# 8chADC.net
KiCad netlist of a schematic drawn in EAGLE
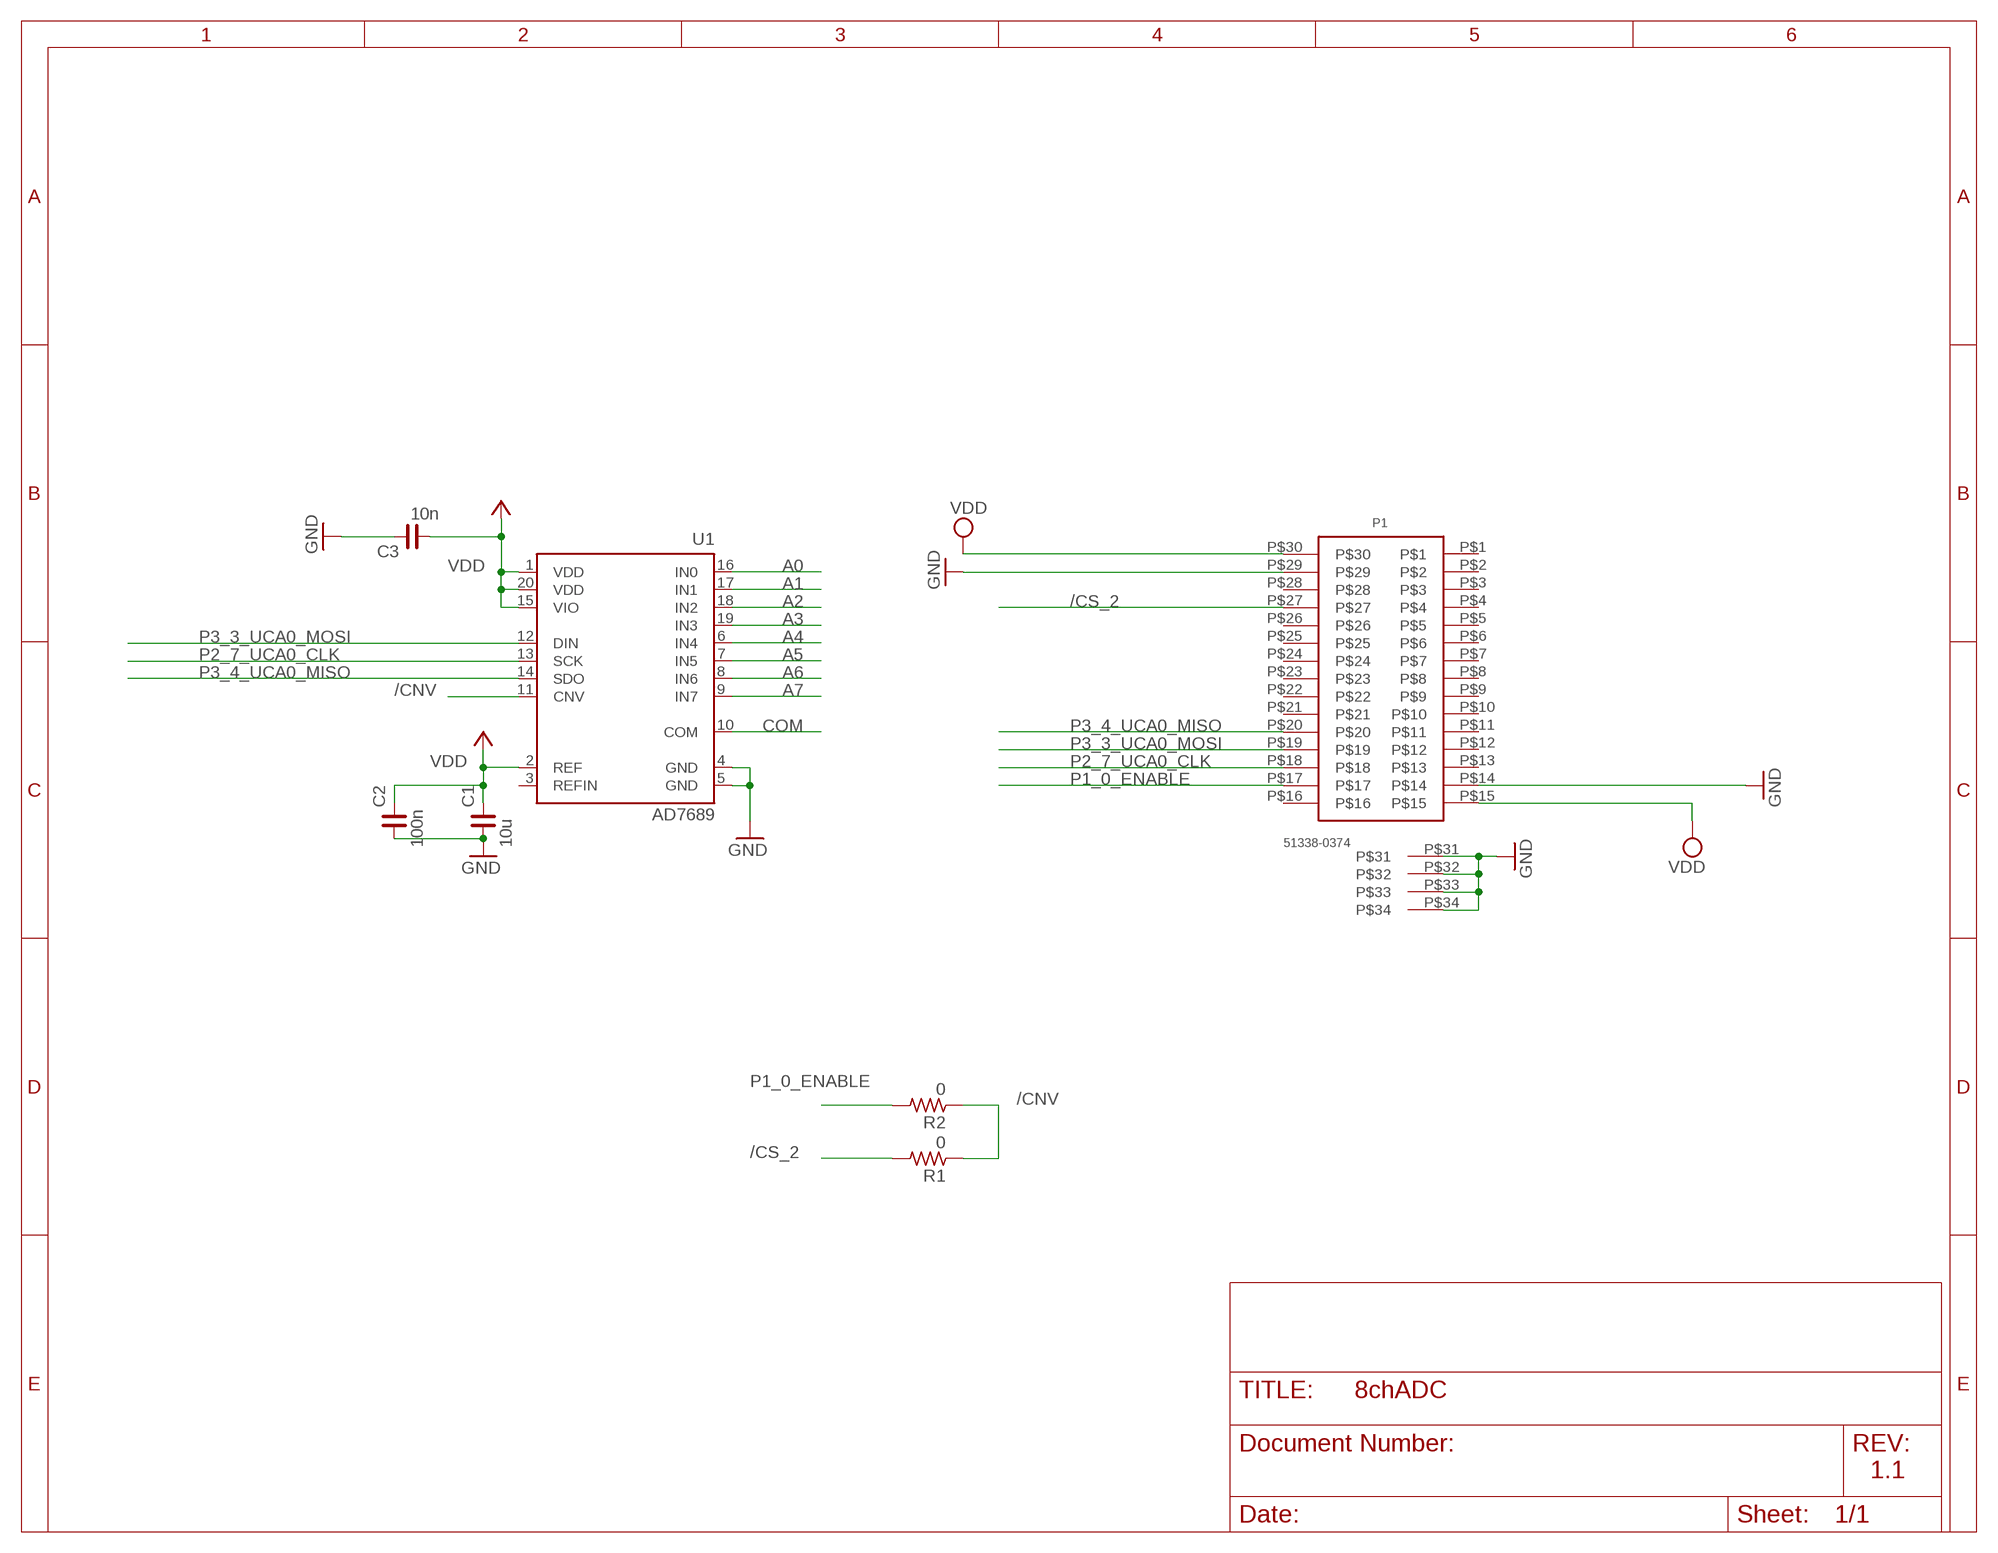
[diagram p0: schematic, sheet 1]

(export (version "E")
  (design (tool "Eeschema 10.0.6"))
  (components
    (comp (ref "C1")
      (value "10u")
      (footprint "eagle-import:C0402")
      (libsource (lib "eagle-import") (part "C_0402"))
    )
    (comp (ref "C2")
      (value "100n")
      (footprint "eagle-import:C0402")
      (libsource (lib "eagle-import") (part "C_0402"))
    )
    (comp (ref "C3")
      (value "10n")
      (footprint "eagle-import:C0402")
      (libsource (lib "eagle-import") (part "C_0402"))
    )
    (comp (ref "P1")
      (value "51338-0374")
      (footprint "eagle-import:51338-0374_RECEPTACLE")
      (libsource (lib "eagle-import") (part "51338-0374_RECEPTACLE"))
    )
    (comp (ref "R1")
      (value "0")
      (footprint "eagle-import:R0402")
      (libsource (lib "eagle-import") (part "R_0402"))
    )
    (comp (ref "R2")
      (value "0")
      (footprint "eagle-import:R0402")
      (libsource (lib "eagle-import") (part "R_0402"))
    )
    (comp (ref "U1")
      (value "AD7689")
      (footprint "eagle-import:LFCSP20")
      (libsource (lib "eagle-import") (part "AD7689"))
    )
  )
  (nets
    (net (code "1") (name "+3V3") (class "Default")
      (node (ref "C1") (pin "2") (pinfunction "2_2") (pintype "passive"))
      (node (ref "C2") (pin "2") (pinfunction "2_2") (pintype "passive"))
      (node (ref "C3") (pin "1") (pinfunction "1_1") (pintype "passive"))
      (node (ref "P1") (pin "P$15") (pinfunction "P$15_P$15") (pintype "bidirectional"))
      (node (ref "P1") (pin "P$30") (pinfunction "P$30_P$30") (pintype "bidirectional"))
      (node (ref "U1") (pin "1") (pinfunction "VDD_1") (pintype "power_in"))
      (node (ref "U1") (pin "15") (pinfunction "VIO_15") (pintype "power_in"))
      (node (ref "U1") (pin "2") (pinfunction "REF_2") (pintype "bidirectional"))
      (node (ref "U1") (pin "20") (pinfunction "VDD_20") (pintype "power_in"))
    )
    (net (code "2") (name "/A0") (class "Default")
      (node (ref "U1") (pin "16") (pinfunction "IN0_16") (pintype "input"))
    )
    (net (code "3") (name "/A1") (class "Default")
      (node (ref "U1") (pin "17") (pinfunction "IN1_17") (pintype "input"))
    )
    (net (code "4") (name "/A2") (class "Default")
      (node (ref "U1") (pin "18") (pinfunction "IN2_18") (pintype "input"))
    )
    (net (code "5") (name "/A3") (class "Default")
      (node (ref "U1") (pin "19") (pinfunction "IN3_19") (pintype "input"))
    )
    (net (code "6") (name "/A4") (class "Default")
      (node (ref "U1") (pin "6") (pinfunction "IN4_6") (pintype "input"))
    )
    (net (code "7") (name "/A5") (class "Default")
      (node (ref "U1") (pin "7") (pinfunction "IN5_7") (pintype "input"))
    )
    (net (code "8") (name "/A6") (class "Default")
      (node (ref "U1") (pin "8") (pinfunction "IN6_8") (pintype "input"))
    )
    (net (code "9") (name "/A7") (class "Default")
      (node (ref "U1") (pin "9") (pinfunction "IN7_9") (pintype "input"))
    )
    (net (code "10") (name "/COM") (class "Default")
      (node (ref "U1") (pin "10") (pinfunction "COM_10") (pintype "input"))
    )
    (net (code "11") (name "/P1_0_ENABLE") (class "Default")
      (node (ref "P1") (pin "P$17") (pinfunction "P$17_P$17") (pintype "bidirectional"))
      (node (ref "R2") (pin "2") (pinfunction "2_2") (pintype "passive"))
    )
    (net (code "12") (name "/P2_7_UCA0_CLK") (class "Default")
      (node (ref "P1") (pin "P$18") (pinfunction "P$18_P$18") (pintype "bidirectional"))
      (node (ref "U1") (pin "13") (pinfunction "SCK_13") (pintype "input"))
    )
    (net (code "13") (name "/P3_3_UCA0_MOSI") (class "Default")
      (node (ref "P1") (pin "P$19") (pinfunction "P$19_P$19") (pintype "bidirectional"))
      (node (ref "U1") (pin "12") (pinfunction "DIN_12") (pintype "input"))
    )
    (net (code "14") (name "/P3_4_UCA0_MISO") (class "Default")
      (node (ref "P1") (pin "P$20") (pinfunction "P$20_P$20") (pintype "bidirectional"))
      (node (ref "U1") (pin "14") (pinfunction "SDO_14") (pintype "output"))
    )
    (net (code "15") (name "/{slash}CNV") (class "Default")
      (node (ref "R1") (pin "1") (pinfunction "1_1") (pintype "passive"))
      (node (ref "R2") (pin "1") (pinfunction "1_1") (pintype "passive"))
      (node (ref "U1") (pin "11") (pinfunction "CNV_11") (pintype "input"))
    )
    (net (code "16") (name "/{slash}CS_2") (class "Default")
      (node (ref "P1") (pin "P$27") (pinfunction "P$27_P$27") (pintype "bidirectional"))
      (node (ref "R1") (pin "2") (pinfunction "2_2") (pintype "passive"))
    )
    (net (code "17") (name "GND") (class "Default")
      (node (ref "C1") (pin "1") (pinfunction "1_1") (pintype "passive"))
      (node (ref "C2") (pin "1") (pinfunction "1_1") (pintype "passive"))
      (node (ref "C3") (pin "2") (pinfunction "2_2") (pintype "passive"))
      (node (ref "P1") (pin "P$14") (pinfunction "P$14_P$14") (pintype "bidirectional"))
      (node (ref "P1") (pin "P$29") (pinfunction "P$29_P$29") (pintype "bidirectional"))
      (node (ref "P1") (pin "P$31") (pinfunction "P$31_P$31") (pintype "bidirectional"))
      (node (ref "P1") (pin "P$32") (pinfunction "P$32_P$32") (pintype "bidirectional"))
      (node (ref "P1") (pin "P$33") (pinfunction "P$33_P$33") (pintype "bidirectional"))
      (node (ref "P1") (pin "P$34") (pinfunction "P$34_P$34") (pintype "bidirectional"))
      (node (ref "U1") (pin "4") (pinfunction "GND_4") (pintype "power_in"))
      (node (ref "U1") (pin "5") (pinfunction "GND_5") (pintype "power_in"))
    )
    (net (code "18") (name "unconnected-(P1-PadP$1)") (class "Default")
      (node (ref "P1") (pin "P$1") (pinfunction "P$1_P$1") (pintype "bidirectional"))
    )
    (net (code "19") (name "unconnected-(P1-PadP$2)") (class "Default")
      (node (ref "P1") (pin "P$2") (pinfunction "P$2_P$2") (pintype "bidirectional"))
    )
    (net (code "20") (name "unconnected-(P1-PadP$3)") (class "Default")
      (node (ref "P1") (pin "P$3") (pinfunction "P$3_P$3") (pintype "bidirectional"))
    )
    (net (code "21") (name "unconnected-(P1-PadP$4)") (class "Default")
      (node (ref "P1") (pin "P$4") (pinfunction "P$4_P$4") (pintype "bidirectional"))
    )
    (net (code "22") (name "unconnected-(P1-PadP$5)") (class "Default")
      (node (ref "P1") (pin "P$5") (pinfunction "P$5_P$5") (pintype "bidirectional"))
    )
    (net (code "23") (name "unconnected-(P1-PadP$6)") (class "Default")
      (node (ref "P1") (pin "P$6") (pinfunction "P$6_P$6") (pintype "bidirectional"))
    )
    (net (code "24") (name "unconnected-(P1-PadP$7)") (class "Default")
      (node (ref "P1") (pin "P$7") (pinfunction "P$7_P$7") (pintype "bidirectional"))
    )
    (net (code "25") (name "unconnected-(P1-PadP$8)") (class "Default")
      (node (ref "P1") (pin "P$8") (pinfunction "P$8_P$8") (pintype "bidirectional"))
    )
    (net (code "26") (name "unconnected-(P1-PadP$9)") (class "Default")
      (node (ref "P1") (pin "P$9") (pinfunction "P$9_P$9") (pintype "bidirectional"))
    )
    (net (code "27") (name "unconnected-(P1-PadP$10)") (class "Default")
      (node (ref "P1") (pin "P$10") (pinfunction "P$10_P$10") (pintype "bidirectional"))
    )
    (net (code "28") (name "unconnected-(P1-PadP$11)") (class "Default")
      (node (ref "P1") (pin "P$11") (pinfunction "P$11_P$11") (pintype "bidirectional"))
    )
    (net (code "29") (name "unconnected-(P1-PadP$12)") (class "Default")
      (node (ref "P1") (pin "P$12") (pinfunction "P$12_P$12") (pintype "bidirectional"))
    )
    (net (code "30") (name "unconnected-(P1-PadP$13)") (class "Default")
      (node (ref "P1") (pin "P$13") (pinfunction "P$13_P$13") (pintype "bidirectional"))
    )
    (net (code "31") (name "unconnected-(P1-PadP$16)") (class "Default")
      (node (ref "P1") (pin "P$16") (pinfunction "P$16_P$16") (pintype "bidirectional"))
    )
    (net (code "32") (name "unconnected-(P1-PadP$21)") (class "Default")
      (node (ref "P1") (pin "P$21") (pinfunction "P$21_P$21") (pintype "bidirectional"))
    )
    (net (code "33") (name "unconnected-(P1-PadP$22)") (class "Default")
      (node (ref "P1") (pin "P$22") (pinfunction "P$22_P$22") (pintype "bidirectional"))
    )
    (net (code "34") (name "unconnected-(P1-PadP$23)") (class "Default")
      (node (ref "P1") (pin "P$23") (pinfunction "P$23_P$23") (pintype "bidirectional"))
    )
    (net (code "35") (name "unconnected-(P1-PadP$24)") (class "Default")
      (node (ref "P1") (pin "P$24") (pinfunction "P$24_P$24") (pintype "bidirectional"))
    )
    (net (code "36") (name "unconnected-(P1-PadP$25)") (class "Default")
      (node (ref "P1") (pin "P$25") (pinfunction "P$25_P$25") (pintype "bidirectional"))
    )
    (net (code "37") (name "unconnected-(P1-PadP$26)") (class "Default")
      (node (ref "P1") (pin "P$26") (pinfunction "P$26_P$26") (pintype "bidirectional"))
    )
    (net (code "38") (name "unconnected-(P1-PadP$28)") (class "Default")
      (node (ref "P1") (pin "P$28") (pinfunction "P$28_P$28") (pintype "bidirectional"))
    )
    (net (code "39") (name "unconnected-(U1-REFIN-Pad3)") (class "Default")
      (node (ref "U1") (pin "3") (pinfunction "REFIN_3") (pintype "bidirectional"))
    )
  )
)
